# ShieldBoard.net
KiCad netlist of a schematic drawn in Altium Designer
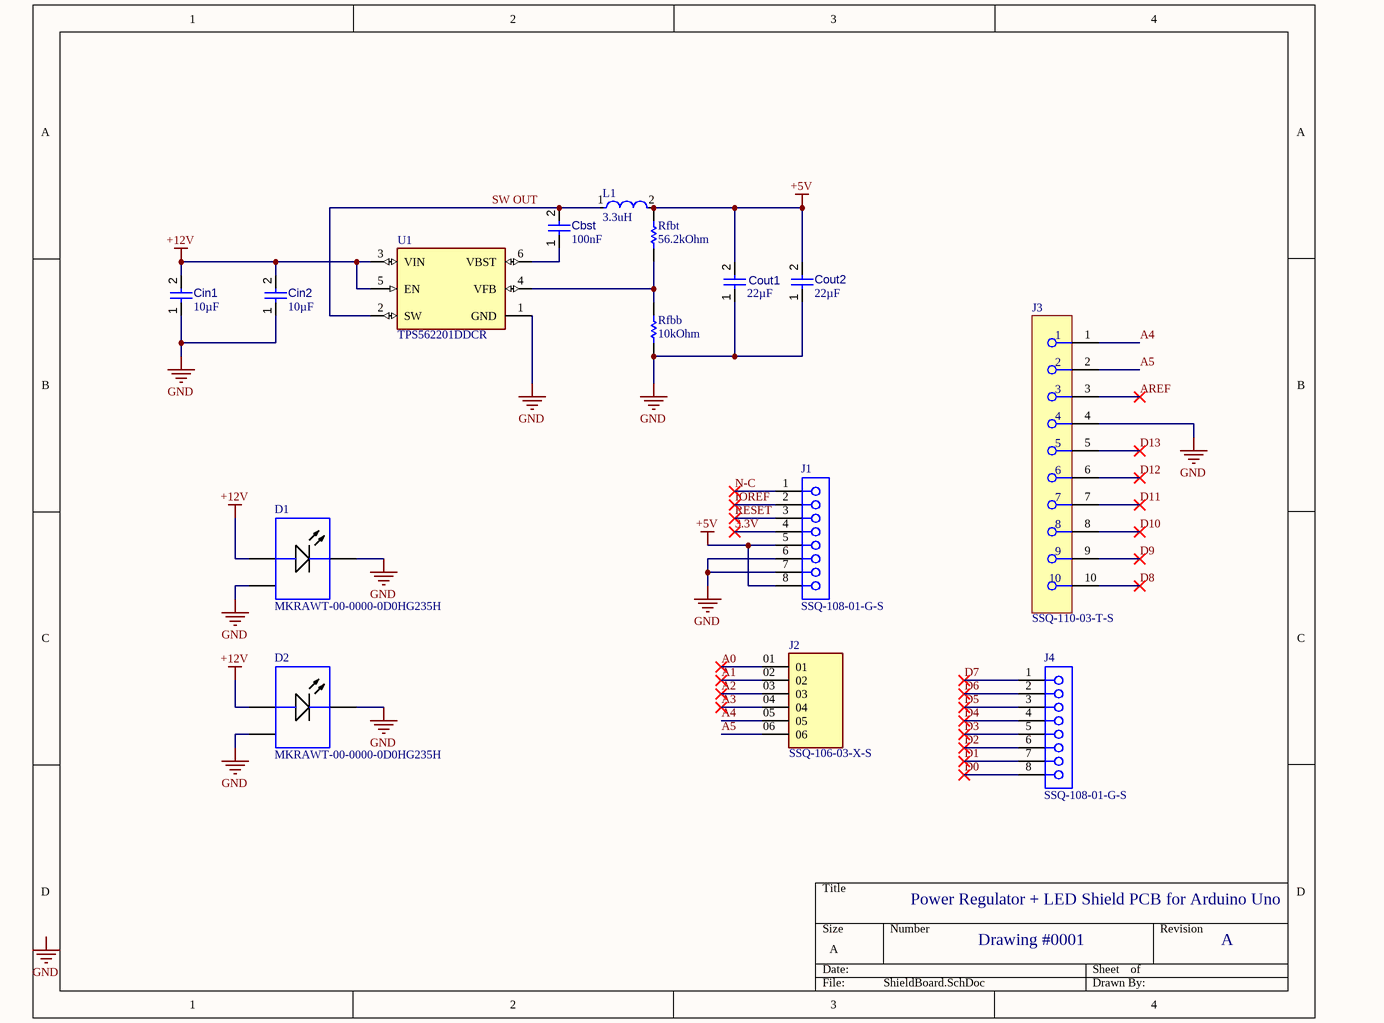
[diagram p0: ShieldBoard.SchDoc]

(export (version "E")
  (design (tool "Eeschema 10.0.6"))
  (components
    (comp (ref "Cbst")
      (value "100nF")
      (footprint "CAPC0402(1005)60_L")
      (description "Chip Capacitor, 100nF +/-20%, 50V, 0402, Thickness 0.6 mm")
      (fields (field (name "TOLERANCE") "10%") (field (name "Comment") "Capacitor 100nF +/-20% 50V 0402"))
      (libsource (lib "Ahamed Hathi") (part "CAP-NP-2"))
    )
    (comp (ref "Cin1")
      (value "10µF")
      (footprint "CAPC0805(2012)145_L")
      (description "Chip Capacitor, 10µF +/-20%, 25V, 0805, Thickness 1.45 mm")
      (fields (field (name "TOLERANCE") "10%") (field (name "Comment") "Capacitor 10µF +/-20% 25V 0805"))
      (libsource (lib "Ahamed Hathi") (part "CAP-NP-2"))
    )
    (comp (ref "Cin2")
      (value "10µF")
      (footprint "CAPC0805(2012)145_L")
      (description "Chip Capacitor, 10µF +/-20%, 25V, 0805, Thickness 1.45 mm")
      (fields (field (name "TOLERANCE") "10%") (field (name "Comment") "Capacitor 10µF +/-20% 25V 0805"))
      (libsource (lib "Ahamed Hathi") (part "CAP-NP-2"))
    )
    (comp (ref "Cout1")
      (value "22µF")
      (footprint "CAPC0805(2012)145_L")
      (description "Chip Capacitor, 22µF +/-40%, 16V, 0805, Thickness 1.45 mm")
      (fields (field (name "TOLERANCE") "5%") (field (name "Comment") "Capacitor 22µF +/-40% 16V 0805"))
      (libsource (lib "Ahamed Hathi") (part "CAP-NP-2"))
    )
    (comp (ref "Cout2")
      (value "22µF")
      (footprint "CAPC0805(2012)145_L")
      (description "Chip Capacitor, 22µF +/-40%, 16V, 0805, Thickness 1.45 mm")
      (fields (field (name "TOLERANCE") "5%") (field (name "Comment") "Capacitor 22µF +/-40% 16V 0805"))
      (libsource (lib "Ahamed Hathi") (part "CAP-NP-2"))
    )
    (comp (ref "D1")
      (value "MKRAWT-00-0000-0D0HG235H")
      (footprint "CREE-MK-R-2_V")
      (description "LED, White, 12 V, 2-Pin SMD, RoHS, Tape and Reel")
      (libsource (lib "Altium Content Vault") (part "LED_WHITE-3"))
    )
    (comp (ref "D2")
      (value "MKRAWT-00-0000-0D0HG235H")
      (footprint "CREE-MK-R-2_V")
      (description "LED, White, 12 V, 2-Pin SMD, RoHS, Tape and Reel")
      (libsource (lib "Altium Content Vault") (part "LED_WHITE-3"))
    )
    (comp (ref "J1")
      (value "SSQ-108-01-G-S")
      (footprint "SMTC-SSQ-108-01-X-S")
      (description "SQ Post Socket, Through-hole, Vertical, -55 to 125 degC, 2.54 mm Pitch, 8-Pin, Female, RoHS")
      (fields (field (name "MANUFACTURER") "Samtec"))
      (libsource (lib "Altium Content Vault") (part "SMTC-SSQ-108-X-X-S-X"))
    )
    (comp (ref "J2")
      (value "SSQ-106-03-X-S")
      (footprint "SAMTEC_SSQ-106-03-X-S")
      (description "SSQ - Samtec 2.54mm Square Tail Single Row Socket Strip 8.5mm Profile - Fast Stock")
      (fields (field (name "MF") "Samtec Inc.") (field (name "MP") "SSQ-106-03-T-S"))
      (libsource (lib "SSQ-106-03-X-S") (part "SSQ-106-03-X-S"))
    )
    (comp (ref "J3")
      (value "SSQ-110-03-T-S")
      (footprint "FP-SSQ-110-03-T-S-MFG")
      (description "SSQ-110-03-T-S Headers & Wire Housings Tiger Buy Socket Strip with Square Tails, 0.100 Pitch")
      (libsource (lib "Altium Content Vault") (part "SSQ-110-03-T-S"))
    )
    (comp (ref "J4")
      (value "SSQ-108-01-G-S")
      (footprint "SMTC-SSQ-108-01-X-S")
      (description "SQ Post Socket, Through-hole, Vertical, -55 to 125 degC, 2.54 mm Pitch, 8-Pin, Female, RoHS")
      (fields (field (name "MANUFACTURER") "Samtec"))
      (libsource (lib "Altium Content Vault") (part "SMTC-SSQ-108-X-X-S-X"))
    )
    (comp (ref "L1")
      (value "3.3uH")
      (footprint "FP-NRS8030-MFG")
      (description "Inductor Power Shielded Wirewound 3.3uH 20% 100KHz Ferrite 4.2A 24.7mΩ DCR T/R")
      (fields (field (name "TOLERANCE") "20%"))
      (libsource (lib "Altium Content Vault") (part "725321dda6339637d4d059423bc1c3c"))
    )
    (comp (ref "Rfbb")
      (value "10kOhm")
      (footprint "RESC1005X40X25LL05T05")
      (description "Chip Resistor, 10 KOhm, +/- 1%, 0.1 W, -55 to 155 degC, 0402 (1005 Metric), RoHS, Tape and Reel")
      (fields (field (name "TOLERANCE") "1%") (field (name "MANUFACTURER") "Panasonic"))
      (libsource (lib "Altium Content Vault") (part "RES-2"))
    )
    (comp (ref "Rfbt")
      (value "56.2kOhm")
      (footprint "RESC0603X28X15NL05T05")
      (fields (field (name "MANUFACTURER") "Vishay Dale") (field (name "PART NUMBER") "CRCW020156K2FNED"))
      (libsource (lib "Altium Content Vault") (part "RES"))
    )
    (comp (ref "U1")
      (value "TPS562201DDCR")
      (footprint "FP-DDC0006A-IPC_C")
      (description "IC REG BUCK ADJ 2A TSOT23-6")
      (libsource (lib "Altium Content Vault") (part "957e164956730ea4bf6293280af19fc"))
    )
  )
  (nets
    (net (code "1") (name "+5V") (class "Default")
      (node (ref "Cout1") (pin "2") (pinfunction "2_2") (pintype "passive"))
      (node (ref "Cout2") (pin "2") (pinfunction "2_2") (pintype "passive"))
      (node (ref "J1") (pin "5") (pinfunction "5_5") (pintype "passive"))
      (node (ref "J1") (pin "8") (pinfunction "8_8") (pintype "passive"))
      (node (ref "L1") (pin "2") (pinfunction "2_2") (pintype "passive"))
      (node (ref "Rfbt") (pin "2") (pinfunction "2_2") (pintype "passive"))
    )
    (net (code "2") (name "+12V") (class "Default")
      (node (ref "Cin1") (pin "2") (pinfunction "2_2") (pintype "passive"))
      (node (ref "Cin2") (pin "2") (pinfunction "2_2") (pintype "passive"))
      (node (ref "D1") (pin "1") (pinfunction "A_1") (pintype "passive"))
      (node (ref "D2") (pin "1") (pinfunction "A_1") (pintype "passive"))
      (node (ref "U1") (pin "3") (pinfunction "VIN_3") (pintype "bidirectional"))
      (node (ref "U1") (pin "5") (pinfunction "EN_5") (pintype "input"))
    )
    (net (code "3") (name "/3.3V") (class "Default")
      (node (ref "J1") (pin "4") (pinfunction "4_4") (pintype "passive+no_connect"))
    )
    (net (code "4") (name "/A0") (class "Default")
      (node (ref "J2") (pin "01") (pinfunction "01_01") (pintype "passive+no_connect"))
    )
    (net (code "5") (name "/A1") (class "Default")
      (node (ref "J2") (pin "02") (pinfunction "02_02") (pintype "passive+no_connect"))
    )
    (net (code "6") (name "/A2") (class "Default")
      (node (ref "J2") (pin "03") (pinfunction "03_03") (pintype "passive+no_connect"))
    )
    (net (code "7") (name "/A3") (class "Default")
      (node (ref "J2") (pin "04") (pinfunction "04_04") (pintype "passive+no_connect"))
    )
    (net (code "8") (name "/A4") (class "Default")
      (node (ref "J2") (pin "05") (pinfunction "05_05") (pintype "passive"))
      (node (ref "J3") (pin "1") (pinfunction "1_1") (pintype "passive"))
    )
    (net (code "9") (name "/A5") (class "Default")
      (node (ref "J2") (pin "06") (pinfunction "06_06") (pintype "passive"))
      (node (ref "J3") (pin "2") (pinfunction "2_2") (pintype "passive"))
    )
    (net (code "10") (name "/AREF") (class "Default")
      (node (ref "J3") (pin "3") (pinfunction "3_3") (pintype "passive+no_connect"))
    )
    (net (code "11") (name "/D0") (class "Default")
      (node (ref "J4") (pin "8") (pinfunction "8_8") (pintype "passive+no_connect"))
    )
    (net (code "12") (name "/D1") (class "Default")
      (node (ref "J4") (pin "7") (pinfunction "7_7") (pintype "passive+no_connect"))
    )
    (net (code "13") (name "/D2") (class "Default")
      (node (ref "J4") (pin "6") (pinfunction "6_6") (pintype "passive+no_connect"))
    )
    (net (code "14") (name "/D3") (class "Default")
      (node (ref "J4") (pin "5") (pinfunction "5_5") (pintype "passive+no_connect"))
    )
    (net (code "15") (name "/D4") (class "Default")
      (node (ref "J4") (pin "4") (pinfunction "4_4") (pintype "passive+no_connect"))
    )
    (net (code "16") (name "/D5") (class "Default")
      (node (ref "J4") (pin "3") (pinfunction "3_3") (pintype "passive+no_connect"))
    )
    (net (code "17") (name "/D6") (class "Default")
      (node (ref "J4") (pin "2") (pinfunction "2_2") (pintype "passive+no_connect"))
    )
    (net (code "18") (name "/D7") (class "Default")
      (node (ref "J4") (pin "1") (pinfunction "1_1") (pintype "passive+no_connect"))
    )
    (net (code "19") (name "/D8") (class "Default")
      (node (ref "J3") (pin "10") (pinfunction "10_10") (pintype "passive+no_connect"))
    )
    (net (code "20") (name "/D9") (class "Default")
      (node (ref "J3") (pin "9") (pinfunction "9_9") (pintype "passive+no_connect"))
    )
    (net (code "21") (name "/D10") (class "Default")
      (node (ref "J3") (pin "8") (pinfunction "8_8") (pintype "passive+no_connect"))
    )
    (net (code "22") (name "/D11") (class "Default")
      (node (ref "J3") (pin "7") (pinfunction "7_7") (pintype "passive+no_connect"))
    )
    (net (code "23") (name "/D12") (class "Default")
      (node (ref "J3") (pin "6") (pinfunction "6_6") (pintype "passive+no_connect"))
    )
    (net (code "24") (name "/D13") (class "Default")
      (node (ref "J3") (pin "5") (pinfunction "5_5") (pintype "passive+no_connect"))
    )
    (net (code "25") (name "/IOREF") (class "Default")
      (node (ref "J1") (pin "2") (pinfunction "2_2") (pintype "passive+no_connect"))
    )
    (net (code "26") (name "/N-C") (class "Default")
      (node (ref "J1") (pin "1") (pinfunction "1_1") (pintype "passive+no_connect"))
    )
    (net (code "27") (name "/RESET") (class "Default")
      (node (ref "J1") (pin "3") (pinfunction "3_3") (pintype "passive+no_connect"))
    )
    (net (code "28") (name "/SW OUT") (class "Default")
      (node (ref "Cbst") (pin "2") (pinfunction "2_2") (pintype "passive"))
      (node (ref "L1") (pin "1") (pinfunction "1_1") (pintype "passive"))
      (node (ref "U1") (pin "2") (pinfunction "SW_2") (pintype "bidirectional"))
    )
    (net (code "29") (name "GND") (class "Default")
      (node (ref "Cin1") (pin "1") (pinfunction "1_1") (pintype "passive"))
      (node (ref "Cin2") (pin "1") (pinfunction "1_1") (pintype "passive"))
      (node (ref "Cout1") (pin "1") (pinfunction "1_1") (pintype "passive"))
      (node (ref "Cout2") (pin "1") (pinfunction "1_1") (pintype "passive"))
      (node (ref "D1") (pin "2") (pinfunction "K_2") (pintype "passive"))
      (node (ref "D1") (pin "3") (pinfunction "EP_3") (pintype "passive"))
      (node (ref "D2") (pin "2") (pinfunction "K_2") (pintype "passive"))
      (node (ref "D2") (pin "3") (pinfunction "EP_3") (pintype "passive"))
      (node (ref "J1") (pin "6") (pinfunction "6_6") (pintype "passive"))
      (node (ref "J1") (pin "7") (pinfunction "7_7") (pintype "passive"))
      (node (ref "J3") (pin "4") (pinfunction "4_4") (pintype "passive"))
      (node (ref "Rfbb") (pin "1") (pinfunction "1_1") (pintype "passive"))
      (node (ref "U1") (pin "1") (pinfunction "GND_1") (pintype "power_in"))
    )
    (net (code "30") (name "Net-(U1-VBST)") (class "Default")
      (node (ref "Cbst") (pin "1") (pinfunction "1_1") (pintype "passive"))
      (node (ref "U1") (pin "6") (pinfunction "VBST_6") (pintype "bidirectional"))
    )
    (net (code "31") (name "Net-(U1-VFB)") (class "Default")
      (node (ref "Rfbb") (pin "2") (pinfunction "2_2") (pintype "passive"))
      (node (ref "Rfbt") (pin "1") (pinfunction "1_1") (pintype "passive"))
      (node (ref "U1") (pin "4") (pinfunction "VFB_4") (pintype "bidirectional"))
    )
  )
)
